# PowerSupply.net
KiCad netlist of a schematic drawn in Altium Designer
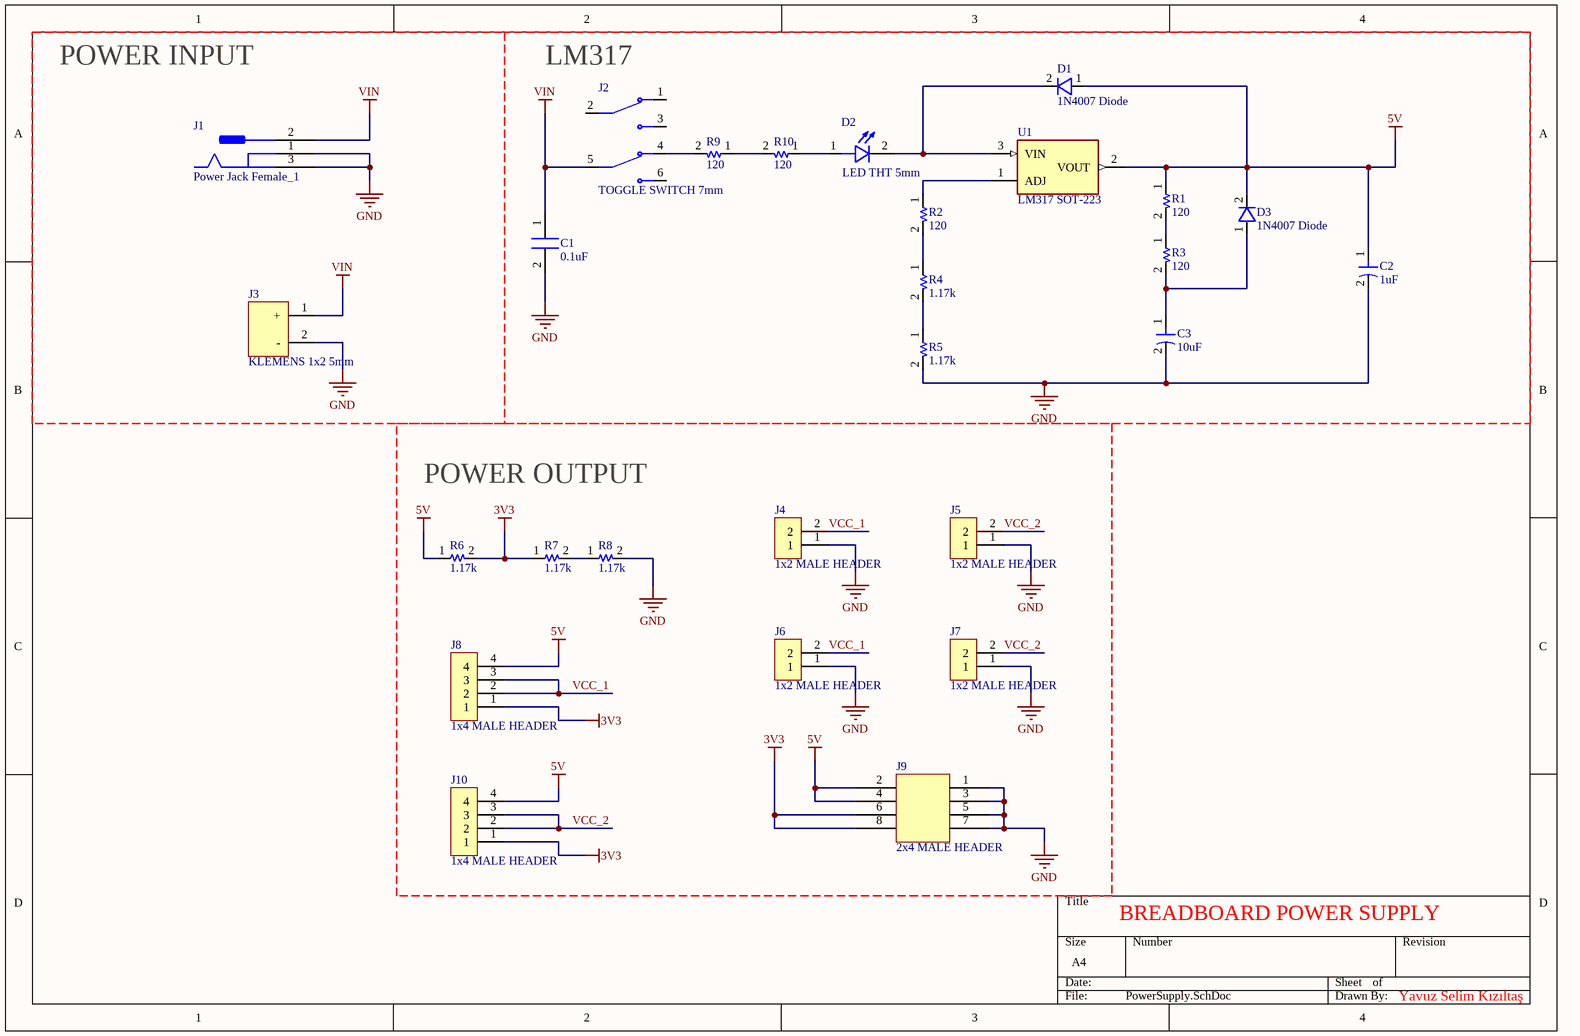
[diagram p0: PowerSupply.SchDoc]

(export (version "E")
  (design (tool "Eeschema 10.0.6"))
  (components
    (comp (ref "C1")
      (value "0.1uF")
      (footprint "MERCIMEK CAPACITOR")
      (libsource (lib "PowerSupply") (part "MERCIMEK CAPACITOR"))
    )
    (comp (ref "C2")
      (value "1uF")
      (footprint "SMD CAPACITOR 3x5 mm")
      (libsource (lib "PowerSupply") (part "SMD CAPACITOR 3x5mm"))
    )
    (comp (ref "C3")
      (value "10uF")
      (footprint "SMD CAPACITOR 4x5 mm")
      (libsource (lib "PowerSupply") (part "SMD CAPACITOR 4x5mm"))
    )
    (comp (ref "D1")
      (value "1N4007 Diode")
      (footprint "1N4007 Diode")
      (libsource (lib "PowerSupply") (part "1N4007 Diode"))
    )
    (comp (ref "D2")
      (value "LED THT 5mm")
      (footprint "LED THT")
      (libsource (lib "PowerSupply") (part "LED THT 5mm"))
    )
    (comp (ref "D3")
      (value "1N4007 Diode")
      (footprint "1N4007 Diode")
      (libsource (lib "PowerSupply") (part "1N4007 Diode"))
    )
    (comp (ref "J1")
      (value "Power Jack Female_1")
      (footprint "Power Jack Female")
      (libsource (lib "PowerSupply") (part "Power Jack Female_1"))
    )
    (comp (ref "J2")
      (value "TOGGLE SWITCH 7mm")
      (footprint "TOGGLE SWITCH 7mm")
      (libsource (lib "PowerSupply") (part "TOGGLE SWITCH 7mm"))
    )
    (comp (ref "J3")
      (value "KLEMENS 1x2 5mm")
      (footprint "KLEMENS 1x2 5mm")
      (libsource (lib "PowerSupply") (part "KLEMENS 1x2 5mm"))
    )
    (comp (ref "J4")
      (value "1x2 MALE HEADER")
      (footprint "1x2 MALE HEADER - duplicate")
      (libsource (lib "PowerSupply") (part "1x2 MALE HEADER"))
    )
    (comp (ref "J5")
      (value "1x2 MALE HEADER")
      (footprint "1x2 MALE HEADER - duplicate")
      (libsource (lib "PowerSupply") (part "1x2 MALE HEADER"))
    )
    (comp (ref "J6")
      (value "1x2 MALE HEADER")
      (footprint "1x2 MALE HEADER - duplicate")
      (libsource (lib "PowerSupply") (part "1x2 MALE HEADER"))
    )
    (comp (ref "J7")
      (value "1x2 MALE HEADER")
      (footprint "1x2 MALE HEADER - duplicate")
      (libsource (lib "PowerSupply") (part "1x2 MALE HEADER"))
    )
    (comp (ref "J8")
      (value "1x4 MALE HEADER")
      (footprint "1x4 MALE HEADER")
      (libsource (lib "PowerSupply") (part "1x4 MALE HEADER"))
    )
    (comp (ref "J9")
      (value "2x4 MALE HEADER")
      (footprint "2x4 Male header")
      (libsource (lib "PowerSupply") (part "2x4 MALE HEADER"))
    )
    (comp (ref "J10")
      (value "1x4 MALE HEADER")
      (footprint "1x4 MALE HEADER")
      (libsource (lib "PowerSupply") (part "1x4 MALE HEADER"))
    )
    (comp (ref "R1")
      (value "120")
      (footprint "R1206 Resıstor")
      (libsource (lib "PowerSupply") (part "R1206"))
    )
    (comp (ref "R2")
      (value "120")
      (footprint "R1206 Resıstor")
      (libsource (lib "PowerSupply") (part "R1206"))
    )
    (comp (ref "R3")
      (value "120")
      (footprint "R1206 Resıstor")
      (libsource (lib "PowerSupply") (part "R1206"))
    )
    (comp (ref "R4")
      (value "1.17k")
      (footprint "RESISTOR THT")
      (libsource (lib "PowerSupply") (part "RESISTOR THT"))
    )
    (comp (ref "R5")
      (value "1.17k")
      (footprint "RESISTOR THT")
      (libsource (lib "PowerSupply") (part "RESISTOR THT"))
    )
    (comp (ref "R6")
      (value "1.17k")
      (footprint "RESISTOR THT")
      (libsource (lib "PowerSupply") (part "RESISTOR THT"))
    )
    (comp (ref "R7")
      (value "1.17k")
      (footprint "RESISTOR THT")
      (libsource (lib "PowerSupply") (part "RESISTOR THT"))
    )
    (comp (ref "R8")
      (value "1.17k")
      (footprint "RESISTOR THT")
      (libsource (lib "PowerSupply") (part "RESISTOR THT"))
    )
    (comp (ref "R9")
      (value "120")
      (footprint "R1206 Resıstor")
      (libsource (lib "PowerSupply") (part "R1206"))
    )
    (comp (ref "R10")
      (value "120")
      (footprint "R1206 Resıstor")
      (libsource (lib "PowerSupply") (part "R1206"))
    )
    (comp (ref "U1")
      (value "LM317 SOT-223")
      (footprint "LM317 SOT-223")
      (libsource (lib "PowerSupply") (part "LM317 SOT-223"))
    )
  )
  (nets
    (net (code "1") (name "/VCC_1") (class "Default")
      (node (ref "J4") (pin "2") (pinfunction "2_2") (pintype "passive"))
      (node (ref "J6") (pin "2") (pinfunction "2_2") (pintype "passive"))
      (node (ref "J8") (pin "2") (pinfunction "2_2") (pintype "passive"))
      (node (ref "J8") (pin "3") (pinfunction "3_3") (pintype "passive"))
    )
    (net (code "2") (name "/VCC_2") (class "Default")
      (node (ref "J10") (pin "2") (pinfunction "2_2") (pintype "passive"))
      (node (ref "J10") (pin "3") (pinfunction "3_3") (pintype "passive"))
      (node (ref "J5") (pin "2") (pinfunction "2_2") (pintype "passive"))
      (node (ref "J7") (pin "2") (pinfunction "2_2") (pintype "passive"))
    )
    (net (code "3") (name "3V3") (class "Default")
      (node (ref "J10") (pin "1") (pinfunction "1_1") (pintype "passive"))
      (node (ref "J8") (pin "1") (pinfunction "1_1") (pintype "passive"))
      (node (ref "J9") (pin "6") (pintype "passive"))
      (node (ref "J9") (pin "8") (pintype "passive"))
      (node (ref "R6") (pin "2") (pinfunction "2_2") (pintype "passive"))
      (node (ref "R7") (pin "1") (pinfunction "1_1") (pintype "passive"))
    )
    (net (code "4") (name "5V") (class "Default")
      (node (ref "C2") (pin "1") (pinfunction "1_1") (pintype "passive"))
      (node (ref "D1") (pin "1") (pintype "passive"))
      (node (ref "D3") (pin "2") (pintype "passive"))
      (node (ref "J10") (pin "4") (pinfunction "4_4") (pintype "passive"))
      (node (ref "J8") (pin "4") (pinfunction "4_4") (pintype "passive"))
      (node (ref "J9") (pin "2") (pintype "passive"))
      (node (ref "J9") (pin "4") (pintype "passive"))
      (node (ref "R1") (pin "1") (pinfunction "1_1") (pintype "passive"))
      (node (ref "R6") (pin "1") (pinfunction "1_1") (pintype "passive"))
      (node (ref "U1") (pin "2") (pinfunction "VOUT_2") (pintype "output"))
    )
    (net (code "5") (name "GND") (class "Default")
      (node (ref "C1") (pin "2") (pinfunction "2_2") (pintype "passive"))
      (node (ref "C2") (pin "2") (pinfunction "2_2") (pintype "passive"))
      (node (ref "C3") (pin "2") (pinfunction "2_2") (pintype "passive"))
      (node (ref "J1") (pin "1") (pinfunction "1_1") (pintype "passive"))
      (node (ref "J1") (pin "3") (pinfunction "3_3") (pintype "passive"))
      (node (ref "J3") (pin "2") (pinfunction "-_2") (pintype "passive"))
      (node (ref "J4") (pin "1") (pinfunction "1_1") (pintype "passive"))
      (node (ref "J5") (pin "1") (pinfunction "1_1") (pintype "passive"))
      (node (ref "J6") (pin "1") (pinfunction "1_1") (pintype "passive"))
      (node (ref "J7") (pin "1") (pinfunction "1_1") (pintype "passive"))
      (node (ref "J9") (pin "1") (pintype "passive"))
      (node (ref "J9") (pin "3") (pintype "passive"))
      (node (ref "J9") (pin "5") (pintype "passive"))
      (node (ref "J9") (pin "7") (pintype "passive"))
      (node (ref "R5") (pin "2") (pinfunction "2_2") (pintype "passive"))
      (node (ref "R8") (pin "2") (pinfunction "2_2") (pintype "passive"))
    )
    (net (code "6") (name "Net-(C3-Pad1)") (class "Default")
      (node (ref "C3") (pin "1") (pinfunction "1_1") (pintype "passive"))
      (node (ref "D3") (pin "1") (pintype "passive"))
      (node (ref "R3") (pin "2") (pinfunction "2_2") (pintype "passive"))
    )
    (net (code "7") (name "Net-(D2-A)") (class "Default")
      (node (ref "D2") (pin "1") (pinfunction "A_1") (pintype "passive"))
      (node (ref "R10") (pin "1") (pinfunction "1_1") (pintype "passive"))
    )
    (net (code "8") (name "Net-(D2-C)") (class "Default")
      (node (ref "D1") (pin "2") (pintype "passive"))
      (node (ref "D2") (pin "2") (pinfunction "C_2") (pintype "passive"))
      (node (ref "U1") (pin "3") (pinfunction "VIN_3") (pintype "input"))
    )
    (net (code "9") (name "Net-(J2-NC2)") (class "Default")
      (node (ref "J2") (pin "4") (pinfunction "NC2_4") (pintype "passive"))
      (node (ref "R9") (pin "2") (pinfunction "2_2") (pintype "passive"))
    )
    (net (code "10") (name "Net-(R1-Pad2)") (class "Default")
      (node (ref "R1") (pin "2") (pinfunction "2_2") (pintype "passive"))
      (node (ref "R3") (pin "1") (pinfunction "1_1") (pintype "passive"))
    )
    (net (code "11") (name "Net-(R2-Pad2)") (class "Default")
      (node (ref "R2") (pin "2") (pinfunction "2_2") (pintype "passive"))
      (node (ref "R4") (pin "1") (pinfunction "1_1") (pintype "passive"))
    )
    (net (code "12") (name "Net-(R4-Pad2)") (class "Default")
      (node (ref "R4") (pin "2") (pinfunction "2_2") (pintype "passive"))
      (node (ref "R5") (pin "1") (pinfunction "1_1") (pintype "passive"))
    )
    (net (code "13") (name "Net-(R7-Pad2)") (class "Default")
      (node (ref "R7") (pin "2") (pinfunction "2_2") (pintype "passive"))
      (node (ref "R8") (pin "1") (pinfunction "1_1") (pintype "passive"))
    )
    (net (code "14") (name "Net-(R10-Pad2)") (class "Default")
      (node (ref "R10") (pin "2") (pinfunction "2_2") (pintype "passive"))
      (node (ref "R9") (pin "1") (pinfunction "1_1") (pintype "passive"))
    )
    (net (code "15") (name "Net-(U1-ADJ)") (class "Default")
      (node (ref "R2") (pin "1") (pinfunction "1_1") (pintype "passive"))
      (node (ref "U1") (pin "1") (pinfunction "ADJ_1") (pintype "passive"))
    )
    (net (code "16") (name "VIN") (class "Default")
      (node (ref "C1") (pin "1") (pinfunction "1_1") (pintype "passive"))
      (node (ref "J1") (pin "2") (pinfunction "VCC_2") (pintype "passive"))
      (node (ref "J2") (pin "5") (pinfunction "COM2_5") (pintype "passive"))
      (node (ref "J3") (pin "1") (pinfunction "+_1") (pintype "passive"))
    )
    (net (code "17") (name "unconnected-(J2-COM1-Pad2)") (class "Default")
      (node (ref "J2") (pin "2") (pinfunction "COM1_2") (pintype "passive"))
    )
    (net (code "18") (name "unconnected-(J2-NC1-Pad1)") (class "Default")
      (node (ref "J2") (pin "1") (pinfunction "NC1_1") (pintype "passive"))
    )
    (net (code "19") (name "unconnected-(J2-NO1-Pad3)") (class "Default")
      (node (ref "J2") (pin "3") (pinfunction "NO1_3") (pintype "passive"))
    )
    (net (code "20") (name "unconnected-(J2-NO2-Pad6)") (class "Default")
      (node (ref "J2") (pin "6") (pinfunction "NO2_6") (pintype "passive"))
    )
  )
)
